# charger.net
KiCad netlist of a schematic drawn in EAGLE
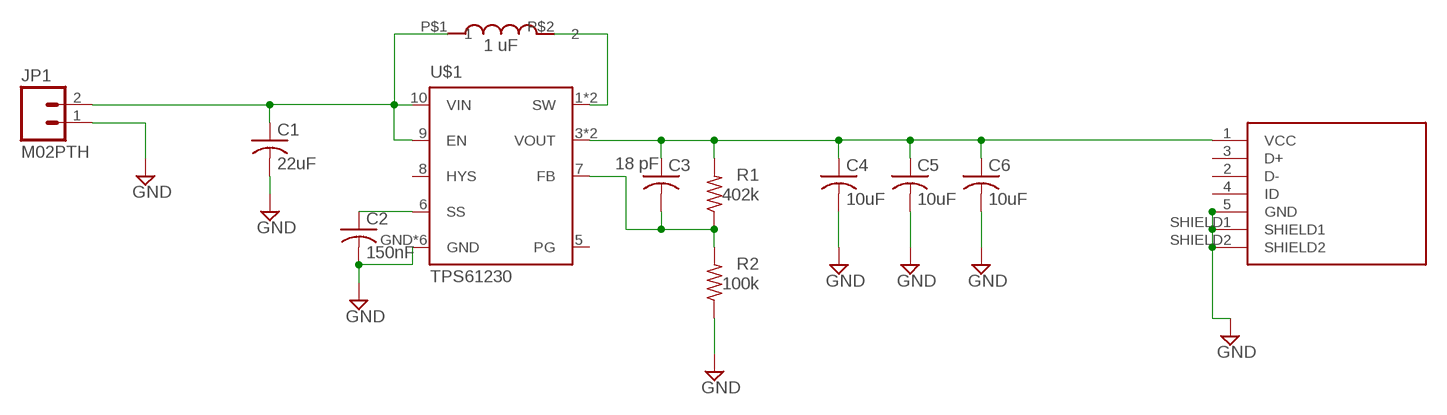
[diagram p0: schematic, sheet 1]

(export (version "E")
  (design (tool "Eeschema 10.0.6"))
  (components
    (comp (ref "C1")
      (value "22uF")
      (footprint "eagle-import:C1206")
      (libsource (lib "eagle-import") (part "resistor_C-USC1206"))
    )
    (comp (ref "C2")
      (value "150nF")
      (footprint "eagle-import:C0603K")
      (libsource (lib "eagle-import") (part "C-USC0603K"))
    )
    (comp (ref "C3")
      (value "18 pF")
      (footprint "eagle-import:C0603K")
      (libsource (lib "eagle-import") (part "resistor_C-USC0603K"))
    )
    (comp (ref "C4")
      (value "10uF")
      (footprint "eagle-import:C0805K")
      (libsource (lib "eagle-import") (part "resistor_C-USC0805K"))
    )
    (comp (ref "C5")
      (value "10uF")
      (footprint "eagle-import:C0805K")
      (libsource (lib "eagle-import") (part "resistor_C-USC0805K"))
    )
    (comp (ref "C6")
      (value "10uF")
      (footprint "eagle-import:C0805K")
      (libsource (lib "eagle-import") (part "resistor_C-USC0805K"))
    )
    (comp (ref "JP1")
      (value "M02PTH")
      (footprint "eagle-import:1X02")
      (libsource (lib "eagle-import") (part "M02PTH"))
    )
    (comp (ref "R1")
      (value "402k")
      (footprint "eagle-import:R0603")
      (libsource (lib "eagle-import") (part "R-US_R0603"))
    )
    (comp (ref "R2")
      (value "100k")
      (footprint "eagle-import:R0603")
      (libsource (lib "eagle-import") (part "R-US_R0603"))
    )
    (comp (ref "U$1")
      (value "TPS61230")
      (footprint "eagle-import:DRC-S-PVSON-N11")
      (libsource (lib "eagle-import") (part "TPS61230"))
    )
    (comp (ref "U$3")
      (value "SRU1028")
      (footprint "eagle-import:SRU1028")
      (libsource (lib "eagle-import") (part "SRU1028"))
    )
    (comp (ref "U$4")
      (value "USB2")
      (footprint "eagle-import:USB2")
      (libsource (lib "eagle-import") (part "USB2"))
    )
  )
  (nets
    (net (code "1") (name "/PG") (class "Default")
      (node (ref "U$1") (pin "5") (pinfunction "PG_5") (pintype "power_in"))
    )
    (net (code "2") (name "GND") (class "Default")
      (node (ref "C1") (pin "2") (pinfunction "2_2") (pintype "passive"))
      (node (ref "C2") (pin "2") (pinfunction "2_2") (pintype "passive"))
      (node (ref "C4") (pin "2") (pinfunction "2_2") (pintype "passive"))
      (node (ref "C5") (pin "2") (pinfunction "2_2") (pintype "passive"))
      (node (ref "C6") (pin "2") (pinfunction "2_2") (pintype "passive"))
      (node (ref "JP1") (pin "1") (pinfunction "1_1") (pintype "passive"))
      (node (ref "R2") (pin "1") (pinfunction "1_1") (pintype "passive"))
      (node (ref "U$1") (pin "GND") (pinfunction "GND_GND") (pintype "power_in"))
      (node (ref "U$1") (pin "GND@1") (pinfunction "GND_GND@1") (pintype "power_in"))
      (node (ref "U$1") (pin "GND@2") (pinfunction "GND_GND@2") (pintype "power_in"))
      (node (ref "U$1") (pin "GND@3") (pinfunction "GND_GND@3") (pintype "power_in"))
      (node (ref "U$1") (pin "GND@4") (pinfunction "GND_GND@4") (pintype "power_in"))
      (node (ref "U$1") (pin "GND@5") (pinfunction "GND_GND@5") (pintype "power_in"))
      (node (ref "U$4") (pin "5") (pinfunction "GND_5") (pintype "bidirectional"))
      (node (ref "U$4") (pin "SHIELD1") (pinfunction "SHIELD1_SHIELD1") (pintype "bidirectional"))
      (node (ref "U$4") (pin "SHIELD2") (pinfunction "SHIELD2_SHIELD2") (pintype "bidirectional"))
    )
    (net (code "3") (name "Net-(U$1-EN)") (class "Default")
      (node (ref "C1") (pin "1") (pinfunction "1_1") (pintype "passive"))
      (node (ref "JP1") (pin "2") (pinfunction "2_2") (pintype "passive"))
      (node (ref "U$1") (pin "10") (pinfunction "VIN_10") (pintype "input"))
      (node (ref "U$1") (pin "9") (pinfunction "EN_9") (pintype "input"))
      (node (ref "U$3") (pin "P$1") (pinfunction "1_P$1") (pintype "bidirectional"))
    )
    (net (code "4") (name "Net-(U$1-FB)") (class "Default")
      (node (ref "C3") (pin "2") (pinfunction "2_2") (pintype "passive"))
      (node (ref "R1") (pin "1") (pinfunction "1_1") (pintype "passive"))
      (node (ref "R2") (pin "2") (pinfunction "2_2") (pintype "passive"))
      (node (ref "U$1") (pin "7") (pinfunction "FB_7") (pintype "input"))
    )
    (net (code "5") (name "Net-(U$1-SS)") (class "Default")
      (node (ref "C2") (pin "1") (pinfunction "1_1") (pintype "passive"))
      (node (ref "U$1") (pin "6") (pinfunction "SS_6") (pintype "input"))
    )
    (net (code "6") (name "Net-(U$3-2)") (class "Default")
      (node (ref "U$1") (pin "1") (pinfunction "SW_1") (pintype "input"))
      (node (ref "U$1") (pin "2") (pinfunction "SW_2") (pintype "input"))
      (node (ref "U$3") (pin "P$2") (pinfunction "2_P$2") (pintype "bidirectional"))
    )
    (net (code "7") (name "Net-(U$4-VCC)") (class "Default")
      (node (ref "C3") (pin "1") (pinfunction "1_1") (pintype "passive"))
      (node (ref "C4") (pin "1") (pinfunction "1_1") (pintype "passive"))
      (node (ref "C5") (pin "1") (pinfunction "1_1") (pintype "passive"))
      (node (ref "C6") (pin "1") (pinfunction "1_1") (pintype "passive"))
      (node (ref "R1") (pin "2") (pinfunction "2_2") (pintype "passive"))
      (node (ref "U$1") (pin "3") (pinfunction "VOUT_3") (pintype "passive"))
      (node (ref "U$1") (pin "4") (pinfunction "VOUT_4") (pintype "passive"))
      (node (ref "U$4") (pin "1") (pinfunction "VCC_1") (pintype "bidirectional"))
    )
    (net (code "8") (name "unconnected-(U$1-HYS-Pad8)") (class "Default")
      (node (ref "U$1") (pin "8") (pinfunction "HYS_8") (pintype "input"))
    )
    (net (code "9") (name "unconnected-(U$4-D+-Pad3)") (class "Default")
      (node (ref "U$4") (pin "3") (pinfunction "D+_3") (pintype "bidirectional"))
    )
    (net (code "10") (name "unconnected-(U$4-D--Pad2)") (class "Default")
      (node (ref "U$4") (pin "2") (pinfunction "D-_2") (pintype "bidirectional"))
    )
    (net (code "11") (name "unconnected-(U$4-ID-Pad4)") (class "Default")
      (node (ref "U$4") (pin "4") (pinfunction "ID_4") (pintype "bidirectional"))
    )
  )
)
